# Expand_Board_no_arduino.net
KiCad netlist of a schematic drawn in Altium Designer
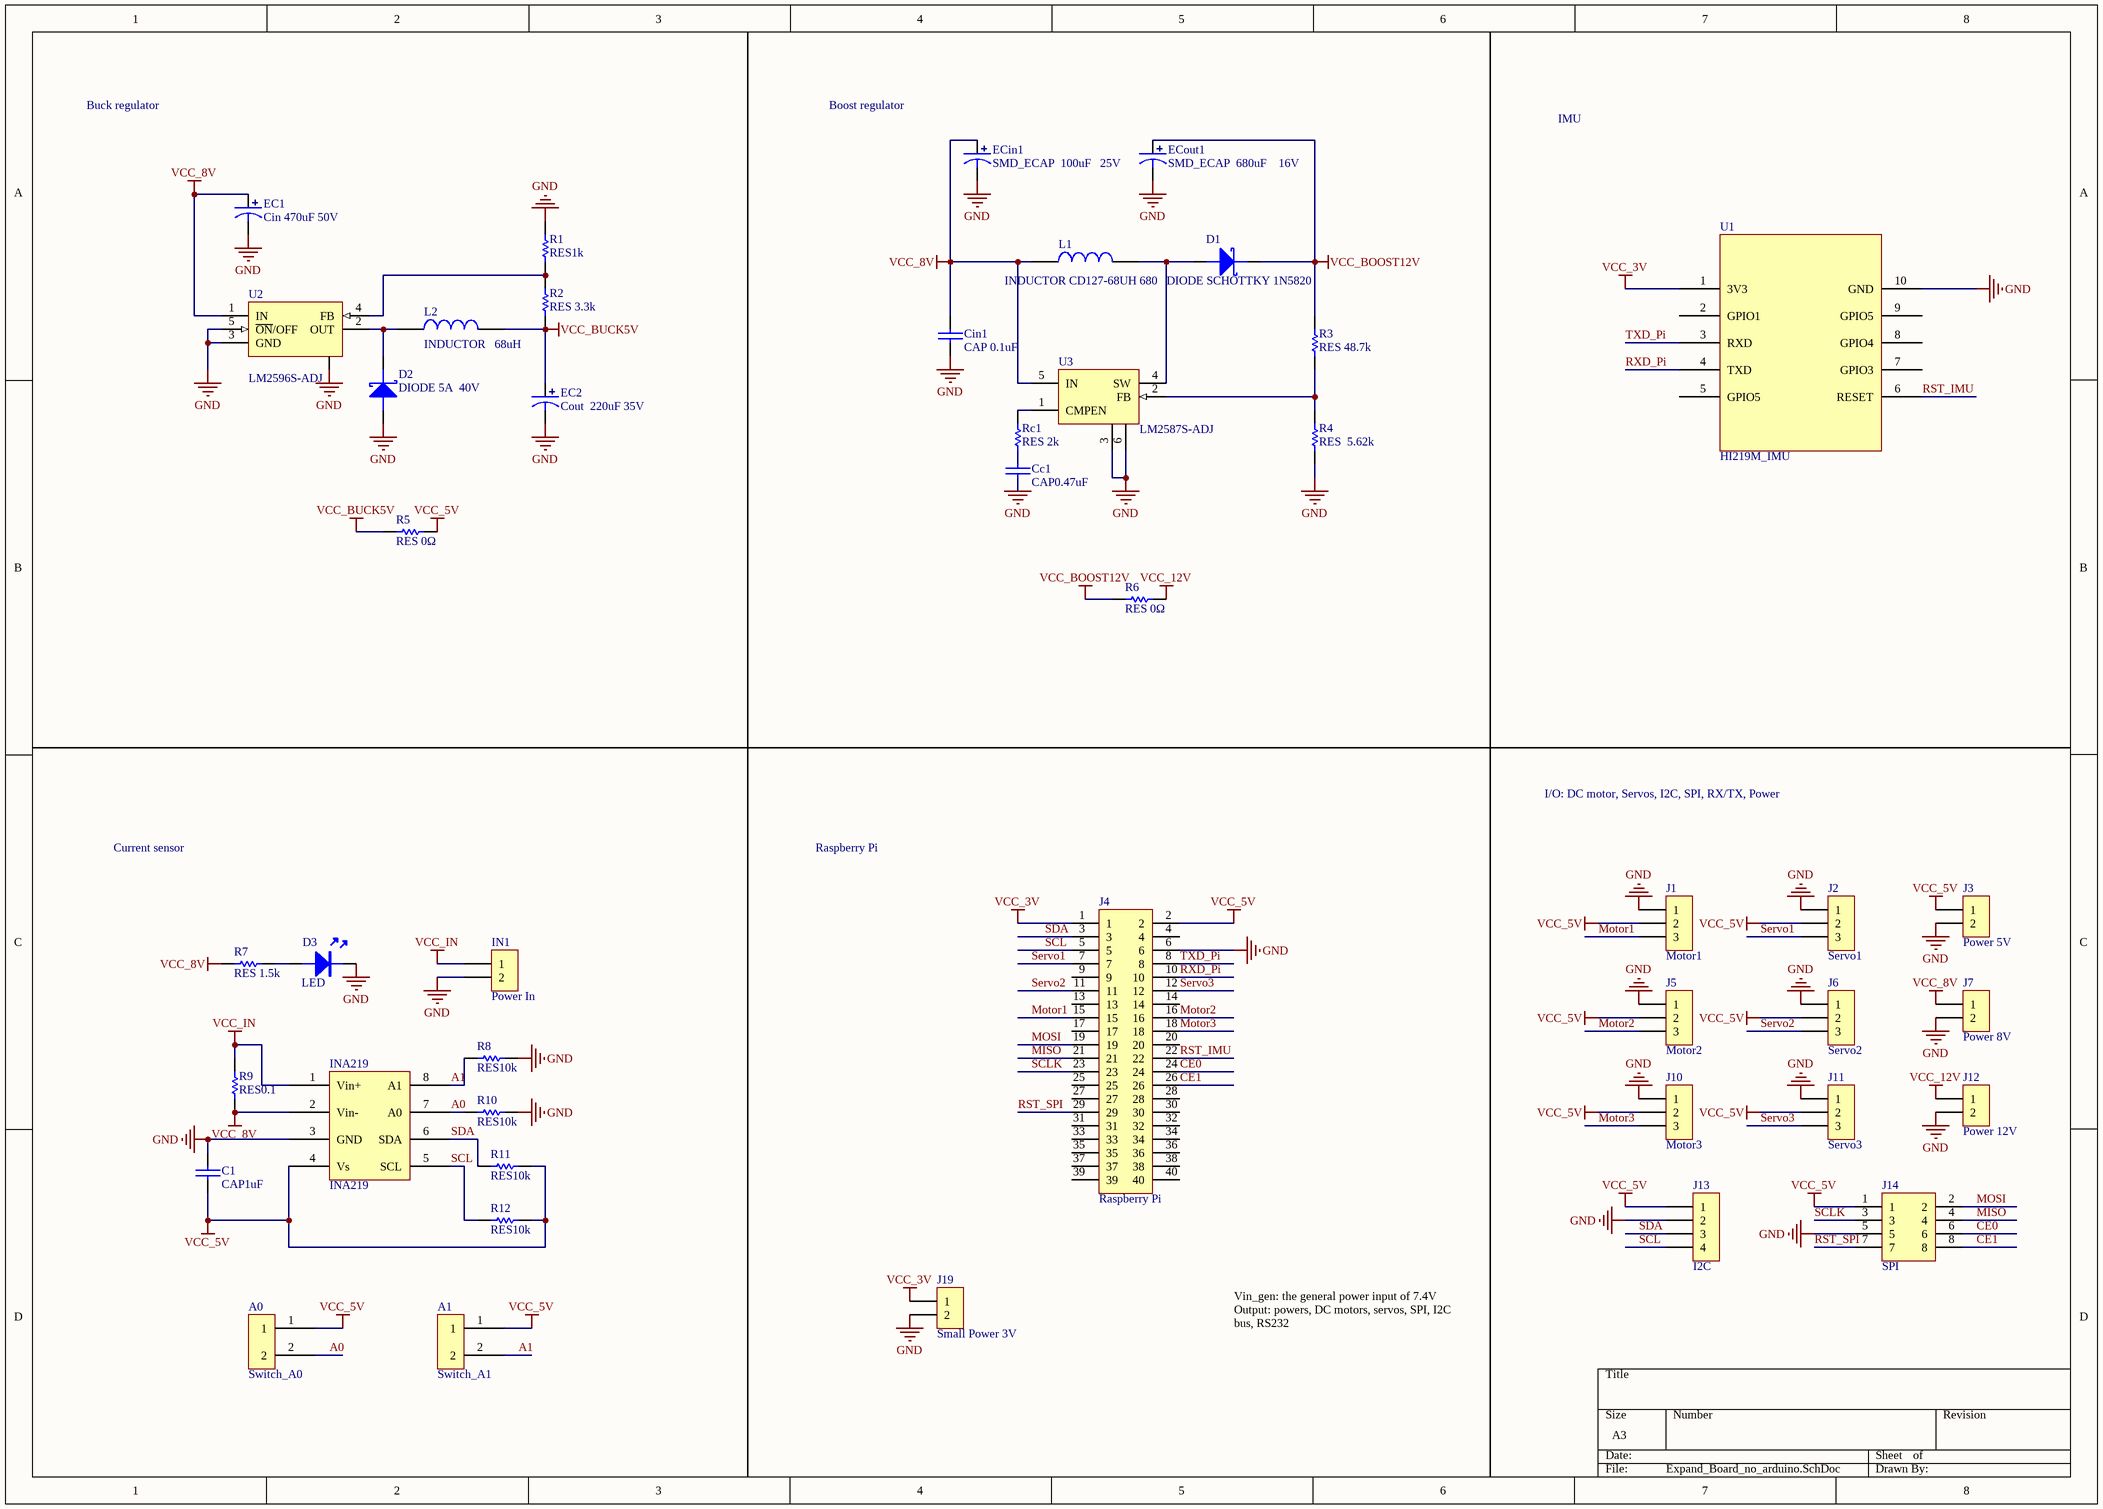
[diagram p0: Expand_Board_no_arduino.SchDoc]

(export (version "E")
  (design (tool "Eeschema 10.0.6"))
  (components
    (comp (ref "A0")
      (value "Switch_A0")
      (footprint "TSOP65P180X145-2N")
      (libsource (lib "Lianxin_Library") (part "Component_1"))
    )
    (comp (ref "A1")
      (value "Switch_A1")
      (footprint "TSOP65P180X145-2N")
      (libsource (lib "Lianxin_Library") (part "Component_1"))
    )
    (comp (ref "C1")
      (value "CAP1uF")
      (footprint "0603C")
      (description "无极性电容")
      (libsource (lib "电容") (part "CAP"))
    )
    (comp (ref "Cc1")
      (value "CAP0.47uF")
      (footprint "0805C")
      (description "无极性电容")
      (libsource (lib "电容") (part "CAP"))
    )
    (comp (ref "Cin1")
      (value "CAP 0.1uF")
      (footprint "0805C")
      (description "无极性电容")
      (libsource (lib "电容") (part "CAP"))
    )
    (comp (ref "D1")
      (value "DIODE SCHOTTKY 1N5820")
      (footprint "SMA/DO-214AC")
      (description "肖特基二极管")
      (libsource (lib "二极管") (part "DIODE SCHOTTKY"))
    )
    (comp (ref "D2")
      (value "DIODE 5A  40V")
      (footprint "SMA/DO-214AC")
      (description "肖特基二极管")
      (libsource (lib "二极管") (part "DIODE SCHOTTKY"))
    )
    (comp (ref "D3") (value "LED") (footprint "LED-0603B") (libsource (lib "LED") (part "LED")))
    (comp (ref "EC1")
      (value "Cin 470uF 50V")
      (footprint "SMD-EC8X8X10")
      (description "贴片电解电容")
      (libsource (lib "电容") (part "SMD_ECAP"))
    )
    (comp (ref "EC2")
      (value "Cout  220uF 35V")
      (footprint "SMD-EC8X8X10")
      (description "贴片电解电容")
      (libsource (lib "电容") (part "SMD_ECAP"))
    )
    (comp (ref "ECin1")
      (value "SMD_ECAP  100uF   25V")
      (footprint "SMD-EC8X8X10")
      (description "贴片电解电容")
      (libsource (lib "电容") (part "SMD_ECAP"))
    )
    (comp (ref "ECout1")
      (value "SMD_ECAP  680uF    16V")
      (footprint "SMD-EC8X8X10")
      (description "贴片电解电容")
      (libsource (lib "电容") (part "SMD_ECAP"))
    )
    (comp (ref "IN1")
      (value "Power In")
      (footprint "Pin HDR1X2/2.54mm-S")
      (libsource (lib "排针") (part "Pin HDR1X2"))
    )
    (comp (ref "INA219") (value "INA219") (footprint "INA219") (libsource (lib "INA219") (part "INA219")))
    (comp (ref "J1")
      (value "Motor1")
      (footprint "Pin HDR1X3/2.54mm-S")
      (libsource (lib "排针") (part "Pin HDR1X3"))
    )
    (comp (ref "J2")
      (value "Servo1")
      (footprint "Pin HDR1X3/2.54mm-S")
      (libsource (lib "排针") (part "Pin HDR1X3"))
    )
    (comp (ref "J3")
      (value "Power 5V")
      (footprint "Pin HDR1X2/2.54mm-S")
      (libsource (lib "排针") (part "Pin HDR1X2"))
    )
    (comp (ref "J4")
      (value "Raspberry Pi")
      (footprint "Pin HDR2X20/2.54mm-S")
      (libsource (lib "排针") (part "Pin HDR2X20"))
    )
    (comp (ref "J5")
      (value "Motor2")
      (footprint "Pin HDR1X3/2.54mm-S")
      (libsource (lib "排针") (part "Pin HDR1X3"))
    )
    (comp (ref "J6")
      (value "Servo2")
      (footprint "Pin HDR1X3/2.54mm-S")
      (libsource (lib "排针") (part "Pin HDR1X3"))
    )
    (comp (ref "J7")
      (value "Power 8V")
      (footprint "Pin HDR1X2/2.54mm-S")
      (libsource (lib "排针") (part "Pin HDR1X2"))
    )
    (comp (ref "J10")
      (value "Motor3")
      (footprint "Pin HDR1X3/2.54mm-S")
      (libsource (lib "排针") (part "Pin HDR1X3"))
    )
    (comp (ref "J11")
      (value "Servo3")
      (footprint "Pin HDR1X3/2.54mm-S")
      (libsource (lib "排针") (part "Pin HDR1X3"))
    )
    (comp (ref "J12")
      (value "Power 12V")
      (footprint "Pin HDR1X2/2.54mm-S")
      (libsource (lib "排针") (part "Pin HDR1X2"))
    )
    (comp (ref "J13")
      (value "I2C")
      (footprint "Pin HDR1X4/2.54mm-S")
      (libsource (lib "排针") (part "Pin HDR1X4"))
    )
    (comp (ref "J14")
      (value "SPI")
      (footprint "Pin HDR2X4/2.54mm-S")
      (libsource (lib "排针") (part "Pin HDR2X4"))
    )
    (comp (ref "J19")
      (value "Small Power 3V")
      (footprint "Pin HDR1X2/2.54mm-S")
      (libsource (lib "排针") (part "Pin HDR1X2"))
    )
    (comp (ref "L1")
      (value "INDUCTOR CD127-68UH 680")
      (footprint "CDRH127")
      (description "INDUCTOR")
      (libsource (lib "电感") (part "INDUCTOR"))
    )
    (comp (ref "L2")
      (value "INDUCTOR   68uH")
      (footprint "CDRH127")
      (description "INDUCTOR")
      (libsource (lib "电感") (part "INDUCTOR"))
    )
    (comp (ref "R1") (value "RES1k") (footprint "0603R") (libsource (lib "电阻") (part "RES")))
    (comp (ref "R2") (value "RES 3.3k") (footprint "0603R") (libsource (lib "电阻") (part "RES")))
    (comp (ref "R3") (value "RES 48.7k") (footprint "0603R") (libsource (lib "电阻") (part "RES")))
    (comp (ref "R4") (value "RES  5.62k") (footprint "0603R") (libsource (lib "电阻") (part "RES")))
    (comp (ref "R5") (value "RES 0Ω") (footprint "0603R") (libsource (lib "电阻") (part "RES")))
    (comp (ref "R6") (value "RES 0Ω") (footprint "0603R") (libsource (lib "电阻") (part "RES")))
    (comp (ref "R7") (value "RES 1.5k") (footprint "0603R") (libsource (lib "电阻") (part "RES")))
    (comp (ref "R8") (value "RES10k") (footprint "0603R") (libsource (lib "电阻") (part "RES")))
    (comp (ref "R9") (value "RES0.1") (footprint "2512R") (libsource (lib "电阻") (part "RES")))
    (comp (ref "R10") (value "RES10k") (footprint "0603R") (libsource (lib "电阻") (part "RES")))
    (comp (ref "R11") (value "RES10k") (footprint "0603R") (libsource (lib "电阻") (part "RES")))
    (comp (ref "R12") (value "RES10k") (footprint "0603R") (libsource (lib "电阻") (part "RES")))
    (comp (ref "Rc1") (value "RES 2k") (footprint "0603R") (libsource (lib "电阻") (part "RES")))
    (comp (ref "U1")
      (value "HI219M_IMU")
      (footprint "SON127P1220X265-10N")
      (libsource (lib "Hi219M_IMU_Lib") (part "Component_1"))
    )
    (comp (ref "U2")
      (value "LM2596S-ADJ")
      (footprint "TO-263-5")
      (description "可调稳压芯片")
      (fields (field (name "PUBLISHER") "Altium Limited"))
      (libsource (lib "fszhang") (part "LM2596S-ADJ"))
    )
    (comp (ref "U3")
      (value "LM2587S-ADJ")
      (footprint "TO-263-5")
      (description "DC升压")
      (fields (field (name "PUBLISHER") "Altium Limited"))
      (libsource (lib "fszhang") (part "LM2577S-ADJ"))
    )
  )
  (nets
    (net (code "1") (name "/A0") (class "Default")
      (node (ref "A0") (pin "2") (pinfunction "2_2") (pintype "passive"))
      (node (ref "INA219") (pin "7") (pinfunction "A0_7") (pintype "passive"))
      (node (ref "R10") (pin "1") (pinfunction "1_1") (pintype "passive"))
    )
    (net (code "2") (name "/A1") (class "Default")
      (node (ref "A1") (pin "2") (pinfunction "2_2") (pintype "passive"))
      (node (ref "INA219") (pin "8") (pinfunction "A1_8") (pintype "passive"))
      (node (ref "R8") (pin "1") (pinfunction "1_1") (pintype "passive"))
    )
    (net (code "3") (name "/CE0") (class "Default")
      (node (ref "J14") (pin "6") (pinfunction "6_6") (pintype "passive"))
      (node (ref "J4") (pin "24") (pinfunction "24_24") (pintype "passive"))
    )
    (net (code "4") (name "/CE1") (class "Default")
      (node (ref "J14") (pin "8") (pinfunction "8_8") (pintype "passive"))
      (node (ref "J4") (pin "26") (pinfunction "26_26") (pintype "passive"))
    )
    (net (code "5") (name "/MISO") (class "Default")
      (node (ref "J14") (pin "4") (pinfunction "4_4") (pintype "passive"))
      (node (ref "J4") (pin "21") (pinfunction "21_21") (pintype "passive"))
    )
    (net (code "6") (name "/MOSI") (class "Default")
      (node (ref "J14") (pin "2") (pinfunction "2_2") (pintype "passive"))
      (node (ref "J4") (pin "19") (pinfunction "19_19") (pintype "passive"))
    )
    (net (code "7") (name "/Motor1") (class "Default")
      (node (ref "J1") (pin "3") (pinfunction "3_3") (pintype "passive"))
      (node (ref "J4") (pin "15") (pinfunction "15_15") (pintype "passive"))
    )
    (net (code "8") (name "/Motor2") (class "Default")
      (node (ref "J4") (pin "16") (pinfunction "16_16") (pintype "passive"))
      (node (ref "J5") (pin "3") (pinfunction "3_3") (pintype "passive"))
    )
    (net (code "9") (name "/Motor3") (class "Default")
      (node (ref "J10") (pin "3") (pinfunction "3_3") (pintype "passive"))
      (node (ref "J4") (pin "18") (pinfunction "18_18") (pintype "passive"))
    )
    (net (code "10") (name "/RST_IMU") (class "Default")
      (node (ref "J4") (pin "22") (pinfunction "22_22") (pintype "passive"))
      (node (ref "U1") (pin "6") (pinfunction "RESET_6") (pintype "passive"))
    )
    (net (code "11") (name "/RST_SPI") (class "Default")
      (node (ref "J14") (pin "7") (pinfunction "7_7") (pintype "passive"))
      (node (ref "J4") (pin "29") (pinfunction "29_29") (pintype "passive"))
    )
    (net (code "12") (name "/RXD_Pi") (class "Default")
      (node (ref "J4") (pin "10") (pinfunction "10_10") (pintype "passive"))
      (node (ref "U1") (pin "4") (pinfunction "TXD_4") (pintype "passive"))
    )
    (net (code "13") (name "/SCL") (class "Default")
      (node (ref "INA219") (pin "5") (pinfunction "SCL_5") (pintype "passive"))
      (node (ref "J13") (pin "4") (pinfunction "4_4") (pintype "passive"))
      (node (ref "J4") (pin "5") (pinfunction "5_5") (pintype "passive"))
      (node (ref "R12") (pin "1") (pinfunction "1_1") (pintype "passive"))
    )
    (net (code "14") (name "/SCLK") (class "Default")
      (node (ref "J14") (pin "3") (pinfunction "3_3") (pintype "passive"))
      (node (ref "J4") (pin "23") (pinfunction "23_23") (pintype "passive"))
    )
    (net (code "15") (name "/SDA") (class "Default")
      (node (ref "INA219") (pin "6") (pinfunction "SDA_6") (pintype "passive"))
      (node (ref "J13") (pin "3") (pinfunction "3_3") (pintype "passive"))
      (node (ref "J4") (pin "3") (pinfunction "3_3") (pintype "passive"))
      (node (ref "R11") (pin "1") (pinfunction "1_1") (pintype "passive"))
    )
    (net (code "16") (name "/Servo1") (class "Default")
      (node (ref "J2") (pin "3") (pinfunction "3_3") (pintype "passive"))
      (node (ref "J4") (pin "7") (pinfunction "7_7") (pintype "passive"))
    )
    (net (code "17") (name "/Servo2") (class "Default")
      (node (ref "J4") (pin "11") (pinfunction "11_11") (pintype "passive"))
      (node (ref "J6") (pin "3") (pinfunction "3_3") (pintype "passive"))
    )
    (net (code "18") (name "/Servo3") (class "Default")
      (node (ref "J11") (pin "3") (pinfunction "3_3") (pintype "passive"))
      (node (ref "J4") (pin "12") (pinfunction "12_12") (pintype "passive"))
    )
    (net (code "19") (name "/TXD_Pi") (class "Default")
      (node (ref "J4") (pin "8") (pinfunction "8_8") (pintype "passive"))
      (node (ref "U1") (pin "3") (pinfunction "RXD_3") (pintype "passive"))
    )
    (net (code "20") (name "GND") (class "Default")
      (node (ref "C1") (pin "2") (pinfunction "2_2") (pintype "passive"))
      (node (ref "Cc1") (pin "1") (pinfunction "1_1") (pintype "passive"))
      (node (ref "Cin1") (pin "1") (pinfunction "1_1") (pintype "passive"))
      (node (ref "D2") (pin "A") (pinfunction "A_A") (pintype "passive"))
      (node (ref "D3") (pin "K") (pinfunction "K_K") (pintype "passive"))
      (node (ref "EC1") (pin "2") (pinfunction "2_2") (pintype "passive"))
      (node (ref "EC2") (pin "2") (pinfunction "2_2") (pintype "passive"))
      (node (ref "ECin1") (pin "2") (pinfunction "2_2") (pintype "passive"))
      (node (ref "ECout1") (pin "2") (pinfunction "2_2") (pintype "passive"))
      (node (ref "IN1") (pin "2") (pinfunction "2_2") (pintype "passive"))
      (node (ref "INA219") (pin "3") (pinfunction "GND_3") (pintype "passive"))
      (node (ref "J1") (pin "1") (pinfunction "1_1") (pintype "passive"))
      (node (ref "J10") (pin "1") (pinfunction "1_1") (pintype "passive"))
      (node (ref "J11") (pin "1") (pinfunction "1_1") (pintype "passive"))
      (node (ref "J12") (pin "2") (pinfunction "2_2") (pintype "passive"))
      (node (ref "J13") (pin "2") (pinfunction "2_2") (pintype "passive"))
      (node (ref "J14") (pin "5") (pinfunction "5_5") (pintype "passive"))
      (node (ref "J19") (pin "2") (pinfunction "2_2") (pintype "passive"))
      (node (ref "J2") (pin "1") (pinfunction "1_1") (pintype "passive"))
      (node (ref "J3") (pin "2") (pinfunction "2_2") (pintype "passive"))
      (node (ref "J4") (pin "6") (pinfunction "6_6") (pintype "passive"))
      (node (ref "J5") (pin "1") (pinfunction "1_1") (pintype "passive"))
      (node (ref "J6") (pin "1") (pinfunction "1_1") (pintype "passive"))
      (node (ref "J7") (pin "2") (pinfunction "2_2") (pintype "passive"))
      (node (ref "R1") (pin "2") (pinfunction "2_2") (pintype "passive"))
      (node (ref "R10") (pin "2") (pinfunction "2_2") (pintype "passive"))
      (node (ref "R4") (pin "1") (pinfunction "1_1") (pintype "passive"))
      (node (ref "R8") (pin "2") (pinfunction "2_2") (pintype "passive"))
      (node (ref "U1") (pin "10") (pinfunction "GND_10") (pintype "passive"))
      (node (ref "U2") (pin "3") (pinfunction "GND_3") (pintype "power_in"))
      (node (ref "U2") (pin "5") (pinfunction "~{ON}/OFF_5") (pintype "input"))
      (node (ref "U2") (pin "6") (pinfunction "6_6") (pintype "power_in"))
      (node (ref "U3") (pin "3") (pinfunction "GND_3") (pintype "power_in"))
      (node (ref "U3") (pin "6") (pinfunction "6_6") (pintype "passive"))
    )
    (net (code "21") (name "Net-(Cc1-Pad2)") (class "Default")
      (node (ref "Cc1") (pin "2") (pinfunction "2_2") (pintype "passive"))
      (node (ref "Rc1") (pin "1") (pinfunction "1_1") (pintype "passive"))
    )
    (net (code "22") (name "Net-(D3-PadA)") (class "Default")
      (node (ref "D3") (pin "A") (pinfunction "A_A") (pintype "passive"))
      (node (ref "R7") (pin "1") (pinfunction "1_1") (pintype "passive"))
    )
    (net (code "23") (name "Net-(U2-FB)") (class "Default")
      (node (ref "R1") (pin "1") (pinfunction "1_1") (pintype "passive"))
      (node (ref "R2") (pin "2") (pinfunction "2_2") (pintype "passive"))
      (node (ref "U2") (pin "4") (pinfunction "FB_4") (pintype "input"))
    )
    (net (code "24") (name "Net-(U2-OUT)") (class "Default")
      (node (ref "D2") (pin "K") (pinfunction "K_K") (pintype "passive"))
      (node (ref "L2") (pin "1") (pinfunction "1_1") (pintype "passive"))
      (node (ref "U2") (pin "2") (pinfunction "OUT_2") (pintype "power_in"))
    )
    (net (code "25") (name "Net-(U3-CMPEN)") (class "Default")
      (node (ref "Rc1") (pin "2") (pinfunction "2_2") (pintype "passive"))
      (node (ref "U3") (pin "1") (pinfunction "CMPEN_1") (pintype "passive"))
    )
    (net (code "26") (name "Net-(U3-FB)") (class "Default")
      (node (ref "R3") (pin "1") (pinfunction "1_1") (pintype "passive"))
      (node (ref "R4") (pin "2") (pinfunction "2_2") (pintype "passive"))
      (node (ref "U3") (pin "2") (pinfunction "FB_2") (pintype "input"))
    )
    (net (code "27") (name "Net-(U3-SW)") (class "Default")
      (node (ref "D1") (pin "A") (pinfunction "A_A") (pintype "passive"))
      (node (ref "L1") (pin "2") (pinfunction "2_2") (pintype "passive"))
      (node (ref "U3") (pin "4") (pinfunction "SW_4") (pintype "power_in"))
    )
    (net (code "28") (name "VCC_3V") (class "Default")
      (node (ref "J19") (pin "1") (pinfunction "1_1") (pintype "passive"))
      (node (ref "J4") (pin "1") (pinfunction "1_1") (pintype "passive"))
      (node (ref "U1") (pin "1") (pinfunction "3V3_1") (pintype "passive"))
    )
    (net (code "29") (name "VCC_5V") (class "Default")
      (node (ref "A0") (pin "1") (pinfunction "1_1") (pintype "passive"))
      (node (ref "A1") (pin "1") (pinfunction "1_1") (pintype "passive"))
      (node (ref "C1") (pin "1") (pinfunction "1_1") (pintype "passive"))
      (node (ref "INA219") (pin "4") (pinfunction "Vs_4") (pintype "passive"))
      (node (ref "J1") (pin "2") (pinfunction "2_2") (pintype "passive"))
      (node (ref "J10") (pin "2") (pinfunction "2_2") (pintype "passive"))
      (node (ref "J11") (pin "2") (pinfunction "2_2") (pintype "passive"))
      (node (ref "J13") (pin "1") (pinfunction "1_1") (pintype "passive"))
      (node (ref "J14") (pin "1") (pinfunction "1_1") (pintype "passive"))
      (node (ref "J2") (pin "2") (pinfunction "2_2") (pintype "passive"))
      (node (ref "J3") (pin "1") (pinfunction "1_1") (pintype "passive"))
      (node (ref "J4") (pin "2") (pinfunction "2_2") (pintype "passive"))
      (node (ref "J5") (pin "2") (pinfunction "2_2") (pintype "passive"))
      (node (ref "J6") (pin "2") (pinfunction "2_2") (pintype "passive"))
      (node (ref "R11") (pin "2") (pinfunction "2_2") (pintype "passive"))
      (node (ref "R12") (pin "2") (pinfunction "2_2") (pintype "passive"))
      (node (ref "R5") (pin "2") (pinfunction "2_2") (pintype "passive"))
    )
    (net (code "30") (name "VCC_8V") (class "Default")
      (node (ref "Cin1") (pin "2") (pinfunction "2_2") (pintype "passive"))
      (node (ref "EC1") (pin "1") (pinfunction "1_1") (pintype "passive"))
      (node (ref "ECin1") (pin "1") (pinfunction "1_1") (pintype "passive"))
      (node (ref "INA219") (pin "2") (pinfunction "Vin-_2") (pintype "passive"))
      (node (ref "J7") (pin "1") (pinfunction "1_1") (pintype "passive"))
      (node (ref "L1") (pin "1") (pinfunction "1_1") (pintype "passive"))
      (node (ref "R7") (pin "2") (pinfunction "2_2") (pintype "passive"))
      (node (ref "R9") (pin "2") (pinfunction "2_2") (pintype "passive"))
      (node (ref "U2") (pin "1") (pinfunction "IN_1") (pintype "power_in"))
      (node (ref "U3") (pin "5") (pinfunction "IN_5") (pintype "power_in"))
    )
    (net (code "31") (name "VCC_12V") (class "Default")
      (node (ref "J12") (pin "1") (pinfunction "1_1") (pintype "passive"))
      (node (ref "R6") (pin "2") (pinfunction "2_2") (pintype "passive"))
    )
    (net (code "32") (name "VCC_BOOST12V") (class "Default")
      (node (ref "D1") (pin "K") (pinfunction "K_K") (pintype "passive"))
      (node (ref "ECout1") (pin "1") (pinfunction "1_1") (pintype "passive"))
      (node (ref "R3") (pin "2") (pinfunction "2_2") (pintype "passive"))
      (node (ref "R6") (pin "1") (pinfunction "1_1") (pintype "passive"))
    )
    (net (code "33") (name "VCC_BUCK5V") (class "Default")
      (node (ref "EC2") (pin "1") (pinfunction "1_1") (pintype "passive"))
      (node (ref "L2") (pin "2") (pinfunction "2_2") (pintype "passive"))
      (node (ref "R2") (pin "1") (pinfunction "1_1") (pintype "passive"))
      (node (ref "R5") (pin "1") (pinfunction "1_1") (pintype "passive"))
    )
    (net (code "34") (name "VCC_IN") (class "Default")
      (node (ref "IN1") (pin "1") (pinfunction "1_1") (pintype "passive"))
      (node (ref "INA219") (pin "1") (pinfunction "Vin+_1") (pintype "passive"))
      (node (ref "R9") (pin "1") (pinfunction "1_1") (pintype "passive"))
    )
    (net (code "35") (name "unconnected-(J4-Pad4)") (class "Default")
      (node (ref "J4") (pin "4") (pinfunction "4_4") (pintype "passive"))
    )
    (net (code "36") (name "unconnected-(J4-Pad9)") (class "Default")
      (node (ref "J4") (pin "9") (pinfunction "9_9") (pintype "passive"))
    )
    (net (code "37") (name "unconnected-(J4-Pad13)") (class "Default")
      (node (ref "J4") (pin "13") (pinfunction "13_13") (pintype "passive"))
    )
    (net (code "38") (name "unconnected-(J4-Pad14)") (class "Default")
      (node (ref "J4") (pin "14") (pinfunction "14_14") (pintype "passive"))
    )
    (net (code "39") (name "unconnected-(J4-Pad17)") (class "Default")
      (node (ref "J4") (pin "17") (pinfunction "17_17") (pintype "passive"))
    )
    (net (code "40") (name "unconnected-(J4-Pad20)") (class "Default")
      (node (ref "J4") (pin "20") (pinfunction "20_20") (pintype "passive"))
    )
    (net (code "41") (name "unconnected-(J4-Pad25)") (class "Default")
      (node (ref "J4") (pin "25") (pinfunction "25_25") (pintype "passive"))
    )
    (net (code "42") (name "unconnected-(J4-Pad27)") (class "Default")
      (node (ref "J4") (pin "27") (pinfunction "27_27") (pintype "passive"))
    )
    (net (code "43") (name "unconnected-(J4-Pad28)") (class "Default")
      (node (ref "J4") (pin "28") (pinfunction "28_28") (pintype "passive"))
    )
    (net (code "44") (name "unconnected-(J4-Pad30)") (class "Default")
      (node (ref "J4") (pin "30") (pinfunction "30_30") (pintype "passive"))
    )
    (net (code "45") (name "unconnected-(J4-Pad31)") (class "Default")
      (node (ref "J4") (pin "31") (pinfunction "31_31") (pintype "passive"))
    )
    (net (code "46") (name "unconnected-(J4-Pad32)") (class "Default")
      (node (ref "J4") (pin "32") (pinfunction "32_32") (pintype "passive"))
    )
    (net (code "47") (name "unconnected-(J4-Pad33)") (class "Default")
      (node (ref "J4") (pin "33") (pinfunction "33_33") (pintype "passive"))
    )
    (net (code "48") (name "unconnected-(J4-Pad34)") (class "Default")
      (node (ref "J4") (pin "34") (pinfunction "34_34") (pintype "passive"))
    )
    (net (code "49") (name "unconnected-(J4-Pad35)") (class "Default")
      (node (ref "J4") (pin "35") (pinfunction "35_35") (pintype "passive"))
    )
    (net (code "50") (name "unconnected-(J4-Pad36)") (class "Default")
      (node (ref "J4") (pin "36") (pinfunction "36_36") (pintype "passive"))
    )
    (net (code "51") (name "unconnected-(J4-Pad37)") (class "Default")
      (node (ref "J4") (pin "37") (pinfunction "37_37") (pintype "passive"))
    )
    (net (code "52") (name "unconnected-(J4-Pad38)") (class "Default")
      (node (ref "J4") (pin "38") (pinfunction "38_38") (pintype "passive"))
    )
    (net (code "53") (name "unconnected-(J4-Pad39)") (class "Default")
      (node (ref "J4") (pin "39") (pinfunction "39_39") (pintype "passive"))
    )
    (net (code "54") (name "unconnected-(J4-Pad40)") (class "Default")
      (node (ref "J4") (pin "40") (pinfunction "40_40") (pintype "passive"))
    )
    (net (code "55") (name "unconnected-(U1-GPIO1-Pad2)") (class "Default")
      (node (ref "U1") (pin "2") (pinfunction "GPIO1_2") (pintype "passive"))
    )
    (net (code "56") (name "unconnected-(U1-GPIO3-Pad7)") (class "Default")
      (node (ref "U1") (pin "7") (pinfunction "GPIO3_7") (pintype "passive"))
    )
    (net (code "57") (name "unconnected-(U1-GPIO4-Pad8)") (class "Default")
      (node (ref "U1") (pin "8") (pinfunction "GPIO4_8") (pintype "passive"))
    )
    (net (code "58") (name "unconnected-(U1-GPIO5-Pad5)") (class "Default")
      (node (ref "U1") (pin "5") (pinfunction "GPIO5_5") (pintype "passive"))
    )
    (net (code "59") (name "unconnected-(U1-GPIO5-Pad9)") (class "Default")
      (node (ref "U1") (pin "9") (pinfunction "GPIO5_9") (pintype "passive"))
    )
  )
)
